# node.net
KiCad netlist of a schematic drawn in EAGLE
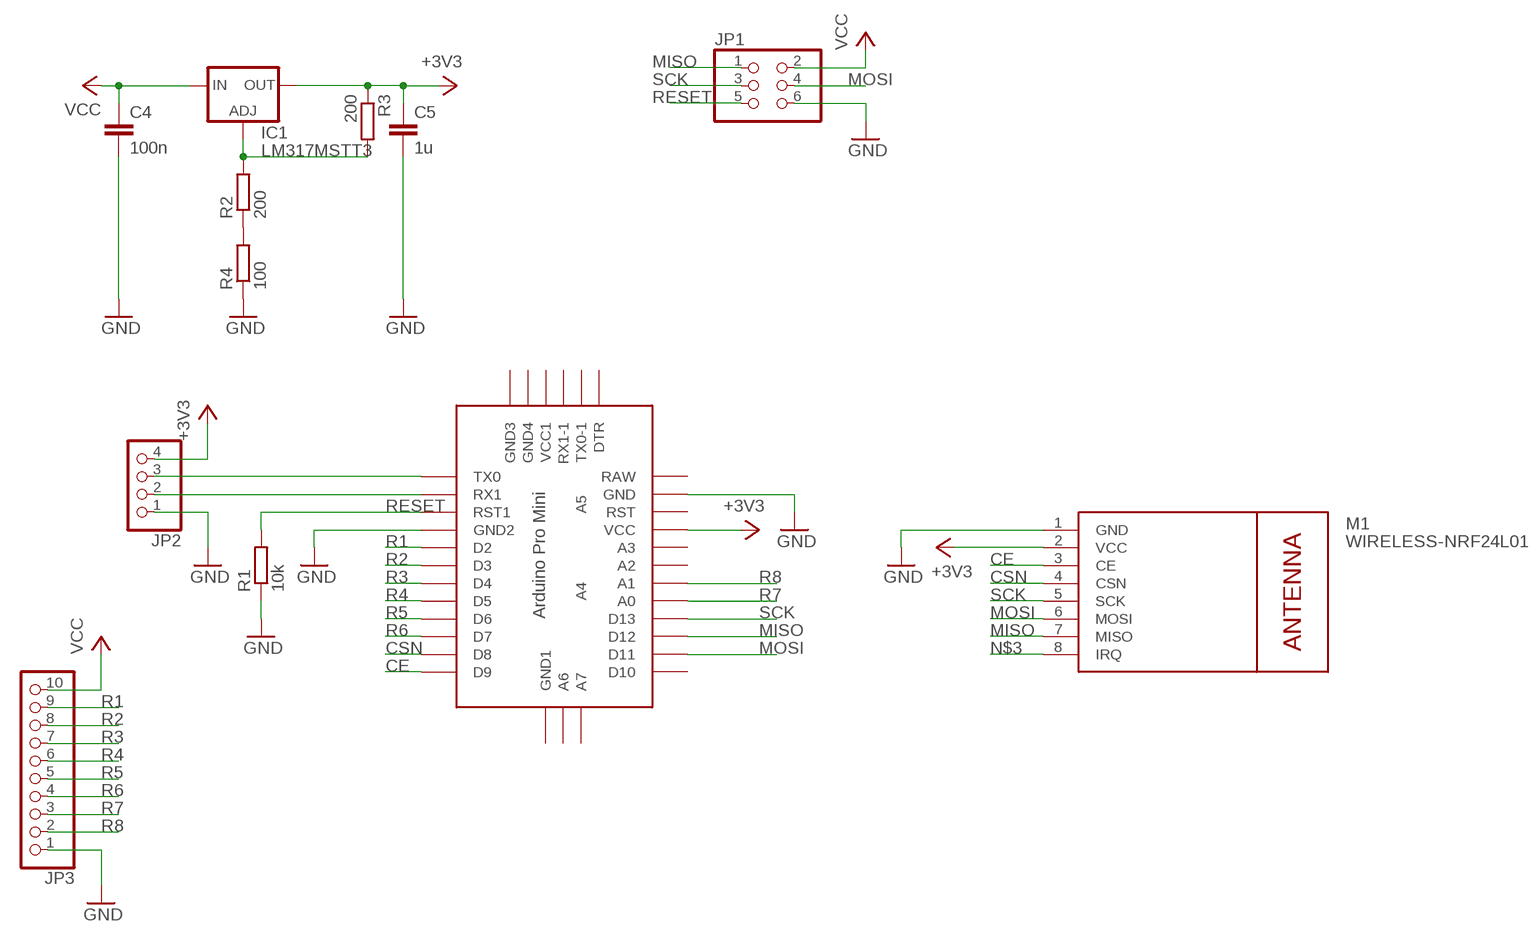
[diagram p0: schematic, sheet 1]

(export (version "E")
  (design (tool "Eeschema 10.0.6"))
  (components
    (comp (ref "C4")
      (value "100n")
      (footprint "eagle-import:C1206")
      (libsource (lib "eagle-import") (part "C-EUC1206"))
    )
    (comp (ref "C5")
      (value "1u")
      (footprint "eagle-import:C1206")
      (libsource (lib "eagle-import") (part "C-EUC1206"))
    )
    (comp (ref "IC1")
      (value "LM317MSTT3")
      (footprint "eagle-import:SOT223")
      (libsource (lib "eagle-import") (part "LM317?MSTT3"))
    )
    (comp (ref "JP1")
      (value "PINHD-2X3")
      (footprint "eagle-import:2X03")
      (libsource (lib "eagle-import") (part "PINHD-2X3"))
    )
    (comp (ref "JP2")
      (value "PINHD-1X4")
      (footprint "eagle-import:1X04")
      (libsource (lib "eagle-import") (part "PINHD-1X4"))
    )
    (comp (ref "JP3")
      (value "PINHD-1X10")
      (footprint "eagle-import:1X10")
      (libsource (lib "eagle-import") (part "PINHD-1X10"))
    )
    (comp (ref "M1")
      (value "WIRELESS-NRF24L01")
      (footprint "eagle-import:WIRELESS-NRF24L01")
      (libsource (lib "eagle-import") (part "WIRELESS-NRF24L01"))
    )
    (comp (ref "R1")
      (value "10k")
      (footprint "eagle-import:M1206")
      (libsource (lib "eagle-import") (part "R-EU_M1206"))
    )
    (comp (ref "R2")
      (value "200")
      (footprint "eagle-import:M1206")
      (libsource (lib "eagle-import") (part "R-EU_M1206"))
    )
    (comp (ref "R3")
      (value "200")
      (footprint "eagle-import:M1206")
      (libsource (lib "eagle-import") (part "R-EU_M1206"))
    )
    (comp (ref "R4")
      (value "100")
      (footprint "eagle-import:M1206")
      (libsource (lib "eagle-import") (part "R-EU_M1206"))
    )
    (comp (ref "U$1")
      (value "ABK-PRO-MINI")
      (footprint "eagle-import:ABK-PRO-MINI")
      (libsource (lib "eagle-import") (part "ABK-PRO-MINI"))
    )
  )
  (nets
    (net (code "1") (name "+3V3") (class "Default")
      (node (ref "C5") (pin "1") (pinfunction "1_1") (pintype "passive"))
      (node (ref "IC1") (pin "4") (pinfunction "OUT_4") (pintype "passive"))
      (node (ref "JP2") (pin "4") (pinfunction "4_4") (pintype "passive"))
      (node (ref "M1") (pin "2") (pinfunction "VCC_2") (pintype "power_in"))
      (node (ref "R3") (pin "1") (pinfunction "1_1") (pintype "passive"))
      (node (ref "U$1") (pin "VCC") (pinfunction "VCC_VCC") (pintype "bidirectional"))
    )
    (net (code "2") (name "/CE") (class "Default")
      (node (ref "M1") (pin "3") (pinfunction "CE_3") (pintype "bidirectional"))
      (node (ref "U$1") (pin "D9") (pinfunction "D9_D9") (pintype "bidirectional"))
    )
    (net (code "3") (name "/CSN") (class "Default")
      (node (ref "M1") (pin "4") (pinfunction "CSN_4") (pintype "bidirectional"))
      (node (ref "U$1") (pin "D8") (pinfunction "D8_D8") (pintype "bidirectional"))
    )
    (net (code "4") (name "/MISO") (class "Default")
      (node (ref "JP1") (pin "1") (pinfunction "1_1") (pintype "passive"))
      (node (ref "M1") (pin "7") (pinfunction "MISO_7") (pintype "bidirectional"))
      (node (ref "U$1") (pin "D12") (pinfunction "D12_D12") (pintype "bidirectional"))
    )
    (net (code "5") (name "/MOSI") (class "Default")
      (node (ref "JP1") (pin "4") (pinfunction "4_4") (pintype "passive"))
      (node (ref "M1") (pin "6") (pinfunction "MOSI_6") (pintype "bidirectional"))
      (node (ref "U$1") (pin "D11") (pinfunction "D11_D11") (pintype "bidirectional"))
    )
    (net (code "6") (name "/N$3") (class "Default")
      (node (ref "M1") (pin "8") (pinfunction "IRQ_8") (pintype "bidirectional"))
    )
    (net (code "7") (name "/R1") (class "Default")
      (node (ref "JP3") (pin "9") (pinfunction "9_9") (pintype "passive"))
      (node (ref "U$1") (pin "D2") (pinfunction "D2_D2") (pintype "bidirectional"))
    )
    (net (code "8") (name "/R2") (class "Default")
      (node (ref "JP3") (pin "8") (pinfunction "8_8") (pintype "passive"))
      (node (ref "U$1") (pin "D3") (pinfunction "D3_D3") (pintype "bidirectional"))
    )
    (net (code "9") (name "/R3") (class "Default")
      (node (ref "JP3") (pin "7") (pinfunction "7_7") (pintype "passive"))
      (node (ref "U$1") (pin "D4") (pinfunction "D4_D4") (pintype "bidirectional"))
    )
    (net (code "10") (name "/R4") (class "Default")
      (node (ref "JP3") (pin "6") (pinfunction "6_6") (pintype "passive"))
      (node (ref "U$1") (pin "D5") (pinfunction "D5_D5") (pintype "bidirectional"))
    )
    (net (code "11") (name "/R5") (class "Default")
      (node (ref "JP3") (pin "5") (pinfunction "5_5") (pintype "passive"))
      (node (ref "U$1") (pin "D6") (pinfunction "D6_D6") (pintype "bidirectional"))
    )
    (net (code "12") (name "/R6") (class "Default")
      (node (ref "JP3") (pin "4") (pinfunction "4_4") (pintype "passive"))
      (node (ref "U$1") (pin "D7") (pinfunction "D7_D7") (pintype "bidirectional"))
    )
    (net (code "13") (name "/R7") (class "Default")
      (node (ref "JP3") (pin "3") (pinfunction "3_3") (pintype "passive"))
      (node (ref "U$1") (pin "A0") (pinfunction "A0_A0") (pintype "bidirectional"))
    )
    (net (code "14") (name "/R8") (class "Default")
      (node (ref "JP3") (pin "2") (pinfunction "2_2") (pintype "passive"))
      (node (ref "U$1") (pin "A1") (pinfunction "A1_A1") (pintype "bidirectional"))
    )
    (net (code "15") (name "/RESET") (class "Default")
      (node (ref "JP1") (pin "5") (pinfunction "5_5") (pintype "passive"))
      (node (ref "R1") (pin "2") (pinfunction "2_2") (pintype "passive"))
      (node (ref "U$1") (pin "RST1") (pinfunction "RST1_RST1") (pintype "bidirectional"))
    )
    (net (code "16") (name "/SCK") (class "Default")
      (node (ref "JP1") (pin "3") (pinfunction "3_3") (pintype "passive"))
      (node (ref "M1") (pin "5") (pinfunction "SCK_5") (pintype "bidirectional"))
      (node (ref "U$1") (pin "D13") (pinfunction "D13_D13") (pintype "bidirectional"))
    )
    (net (code "17") (name "GND") (class "Default")
      (node (ref "C4") (pin "2") (pinfunction "2_2") (pintype "passive"))
      (node (ref "C5") (pin "2") (pinfunction "2_2") (pintype "passive"))
      (node (ref "JP1") (pin "6") (pinfunction "6_6") (pintype "passive"))
      (node (ref "JP2") (pin "1") (pinfunction "1_1") (pintype "passive"))
      (node (ref "JP3") (pin "1") (pinfunction "1_1") (pintype "passive"))
      (node (ref "M1") (pin "1") (pinfunction "GND_1") (pintype "power_in"))
      (node (ref "R1") (pin "1") (pinfunction "1_1") (pintype "passive"))
      (node (ref "R4") (pin "1") (pinfunction "1_1") (pintype "passive"))
      (node (ref "U$1") (pin "GND") (pinfunction "GND_GND") (pintype "bidirectional"))
      (node (ref "U$1") (pin "GND1") (pinfunction "GND2_GND1") (pintype "bidirectional"))
    )
    (net (code "18") (name "Net-(IC1-ADJ)") (class "Default")
      (node (ref "IC1") (pin "1") (pinfunction "ADJ_1") (pintype "input"))
      (node (ref "R2") (pin "2") (pinfunction "2_2") (pintype "passive"))
      (node (ref "R3") (pin "2") (pinfunction "2_2") (pintype "passive"))
    )
    (net (code "19") (name "Net-(JP2-Pad2)") (class "Default")
      (node (ref "JP2") (pin "2") (pinfunction "2_2") (pintype "passive"))
      (node (ref "U$1") (pin "RX1") (pinfunction "RX1_RX1") (pintype "bidirectional"))
    )
    (net (code "20") (name "Net-(JP2-Pad3)") (class "Default")
      (node (ref "JP2") (pin "3") (pinfunction "3_3") (pintype "passive"))
      (node (ref "U$1") (pin "TX0") (pinfunction "TX0_TX0") (pintype "bidirectional"))
    )
    (net (code "21") (name "Net-(R2-Pad1)") (class "Default")
      (node (ref "R2") (pin "1") (pinfunction "1_1") (pintype "passive"))
      (node (ref "R4") (pin "2") (pinfunction "2_2") (pintype "passive"))
    )
    (net (code "22") (name "VCC") (class "Default")
      (node (ref "C4") (pin "1") (pinfunction "1_1") (pintype "passive"))
      (node (ref "IC1") (pin "3") (pinfunction "IN_3") (pintype "input"))
      (node (ref "JP1") (pin "2") (pinfunction "2_2") (pintype "passive"))
      (node (ref "JP3") (pin "10") (pinfunction "10_10") (pintype "passive"))
    )
    (net (code "23") (name "unconnected-(U$1-GND1-PadGND4)") (class "Default")
      (node (ref "U$1") (pin "GND4") (pinfunction "GND1_GND4") (pintype "bidirectional"))
    )
    (net (code "24") (name "unconnected-(U$1-GND3-PadGND2)") (class "Default")
      (node (ref "U$1") (pin "GND2") (pinfunction "GND3_GND2") (pintype "bidirectional"))
    )
    (net (code "25") (name "unconnected-(U$1-GND4-PadGND3)") (class "Default")
      (node (ref "U$1") (pin "GND3") (pinfunction "GND4_GND3") (pintype "bidirectional"))
    )
    (net (code "26") (name "unconnected-(U$1-PadA2)") (class "Default")
      (node (ref "U$1") (pin "A2") (pinfunction "A2_A2") (pintype "bidirectional"))
    )
    (net (code "27") (name "unconnected-(U$1-PadA3)") (class "Default")
      (node (ref "U$1") (pin "A3") (pinfunction "A3_A3") (pintype "bidirectional"))
    )
    (net (code "28") (name "unconnected-(U$1-PadA4)") (class "Default")
      (node (ref "U$1") (pin "A4") (pinfunction "A4_A4") (pintype "bidirectional"))
    )
    (net (code "29") (name "unconnected-(U$1-PadA5)") (class "Default")
      (node (ref "U$1") (pin "A5") (pinfunction "A5_A5") (pintype "bidirectional"))
    )
    (net (code "30") (name "unconnected-(U$1-PadA6)") (class "Default")
      (node (ref "U$1") (pin "A6") (pinfunction "A6_A6") (pintype "bidirectional"))
    )
    (net (code "31") (name "unconnected-(U$1-PadA7)") (class "Default")
      (node (ref "U$1") (pin "A7") (pinfunction "A7_A7") (pintype "bidirectional"))
    )
    (net (code "32") (name "unconnected-(U$1-PadD10)") (class "Default")
      (node (ref "U$1") (pin "D10") (pinfunction "D10_D10") (pintype "bidirectional"))
    )
    (net (code "33") (name "unconnected-(U$1-PadDTR)") (class "Default")
      (node (ref "U$1") (pin "DTR") (pinfunction "DTR_DTR") (pintype "bidirectional"))
    )
    (net (code "34") (name "unconnected-(U$1-PadRAW)") (class "Default")
      (node (ref "U$1") (pin "RAW") (pinfunction "RAW_RAW") (pintype "bidirectional"))
    )
    (net (code "35") (name "unconnected-(U$1-PadRST)") (class "Default")
      (node (ref "U$1") (pin "RST") (pinfunction "RST_RST") (pintype "bidirectional"))
    )
    (net (code "36") (name "unconnected-(U$1-PadRX1-1)") (class "Default")
      (node (ref "U$1") (pin "RX1-1") (pinfunction "RX1-1_RX1-1") (pintype "bidirectional"))
    )
    (net (code "37") (name "unconnected-(U$1-PadTX0-1)") (class "Default")
      (node (ref "U$1") (pin "TX0-1") (pinfunction "TX0-1_TX0-1") (pintype "bidirectional"))
    )
    (net (code "38") (name "unconnected-(U$1-PadVCC1)") (class "Default")
      (node (ref "U$1") (pin "VCC1") (pinfunction "VCC1_VCC1") (pintype "bidirectional"))
    )
  )
)
